# RS232_NPN_PNP_FTDI_2.net
KiCad netlist of a schematic drawn in EAGLE
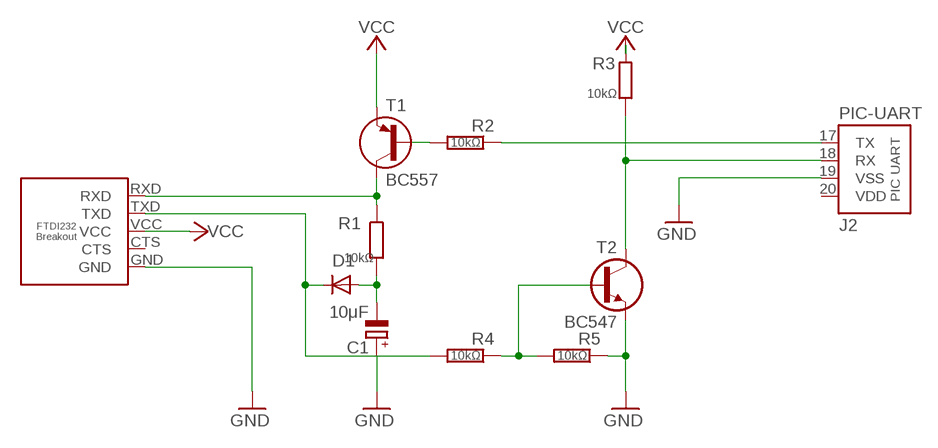
[diagram p0: schematic, sheet 1]

(export (version "E")
  (design (tool "Eeschema 10.0.6"))
  (components
    (comp (ref "C1")
      (value "10μF")
      (footprint "eagle-import:E2.5-4_V")
      (libsource (lib "eagle-import") (part "CPOLE2,5-4/V"))
    )
    (comp (ref "D1")
      (value "1N4148")
      (footprint "eagle-import:DO34-5V")
      (libsource (lib "eagle-import") (part "1N414834-5V"))
    )
    (comp (ref "J1")
      (value "FTDI232-BO-5P-L")
      (footprint "eagle-import:FTDI232-BO-5-L")
      (libsource (lib "eagle-import") (part "FTDI232-BO-5P-L"))
    )
    (comp (ref "J2")
      (value "PIC-UART")
      (footprint "eagle-import:PIC-UART")
      (libsource (lib "eagle-import") (part "PIC-UART"))
    )
    (comp (ref "R1")
      (value "10kΩ")
      (footprint "eagle-import:0202_7-V")
      (libsource (lib "eagle-import") (part "R0202/7-V"))
    )
    (comp (ref "R2")
      (value "10kΩ")
      (footprint "eagle-import:0202_5")
      (libsource (lib "eagle-import") (part "R0202/5"))
    )
    (comp (ref "R3")
      (value "10kΩ")
      (footprint "eagle-import:0202_5")
      (libsource (lib "eagle-import") (part "R0202/5"))
    )
    (comp (ref "R4")
      (value "10kΩ")
      (footprint "eagle-import:0202_5")
      (libsource (lib "eagle-import") (part "R0202/5"))
    )
    (comp (ref "R5")
      (value "10kΩ")
      (footprint "eagle-import:0202_5")
      (libsource (lib "eagle-import") (part "R0202/5"))
    )
    (comp (ref "T1")
      (value "BC557")
      (footprint "eagle-import:TO92-CBE")
      (libsource (lib "eagle-import") (part "BC557CBE"))
    )
    (comp (ref "T2")
      (value "BC547")
      (footprint "eagle-import:TO92-CBE")
      (libsource (lib "eagle-import") (part "BC547CBE"))
    )
  )
  (nets
    (net (code "1") (name "GND") (class "Default")
      (node (ref "C1") (pin "+") (pinfunction "+_+") (pintype "passive"))
      (node (ref "J1") (pin "GND") (pinfunction "GND_GND") (pintype "bidirectional"))
      (node (ref "J2") (pin "19") (pinfunction "VSS_19") (pintype "passive"))
      (node (ref "R5") (pin "1") (pinfunction "1_1") (pintype "passive"))
      (node (ref "T2") (pin "E") (pinfunction "E_E") (pintype "passive"))
    )
    (net (code "2") (name "Net-(C1-Pad-)") (class "Default")
      (node (ref "C1") (pin "-") (pinfunction "-_-") (pintype "passive"))
      (node (ref "D1") (pin "A") (pinfunction "A_A") (pintype "passive"))
      (node (ref "R1") (pin "2") (pinfunction "2_2") (pintype "passive"))
    )
    (net (code "3") (name "Net-(D1-PadC)") (class "Default")
      (node (ref "D1") (pin "C") (pinfunction "C_C") (pintype "passive"))
      (node (ref "J1") (pin "TXD") (pinfunction "TXD_TXD") (pintype "bidirectional"))
      (node (ref "R4") (pin "2") (pinfunction "2_2") (pintype "passive"))
    )
    (net (code "4") (name "Net-(J1-PadRXD)") (class "Default")
      (node (ref "J1") (pin "RXD") (pinfunction "RXD_RXD") (pintype "bidirectional"))
      (node (ref "R1") (pin "1") (pinfunction "1_1") (pintype "passive"))
      (node (ref "T1") (pin "C") (pinfunction "C_C") (pintype "passive"))
    )
    (net (code "5") (name "Net-(J2-RX)") (class "Default")
      (node (ref "J2") (pin "18") (pinfunction "RX_18") (pintype "passive"))
      (node (ref "R3") (pin "1") (pinfunction "1_1") (pintype "passive"))
      (node (ref "T2") (pin "C") (pinfunction "C_C") (pintype "passive"))
    )
    (net (code "6") (name "Net-(J2-TX)") (class "Default")
      (node (ref "J2") (pin "17") (pinfunction "TX_17") (pintype "passive"))
      (node (ref "R2") (pin "1") (pinfunction "1_1") (pintype "passive"))
    )
    (net (code "7") (name "Net-(R2-Pad2)") (class "Default")
      (node (ref "R2") (pin "2") (pinfunction "2_2") (pintype "passive"))
      (node (ref "T1") (pin "B") (pinfunction "B_B") (pintype "passive"))
    )
    (net (code "8") (name "Net-(R4-Pad1)") (class "Default")
      (node (ref "R4") (pin "1") (pinfunction "1_1") (pintype "passive"))
      (node (ref "R5") (pin "2") (pinfunction "2_2") (pintype "passive"))
      (node (ref "T2") (pin "B") (pinfunction "B_B") (pintype "passive"))
    )
    (net (code "9") (name "VCC") (class "Default")
      (node (ref "J1") (pin "VCC") (pinfunction "VCC_VCC") (pintype "bidirectional"))
      (node (ref "R3") (pin "2") (pinfunction "2_2") (pintype "passive"))
      (node (ref "T1") (pin "E") (pinfunction "E_E") (pintype "passive"))
    )
    (net (code "10") (name "unconnected-(J1-PadCTS)") (class "Default")
      (node (ref "J1") (pin "CTS") (pinfunction "CTS_CTS") (pintype "bidirectional"))
    )
    (net (code "11") (name "unconnected-(J2-VDD-Pad20)") (class "Default")
      (node (ref "J2") (pin "20") (pinfunction "VDD_20") (pintype "passive"))
    )
  )
)
